# REGULATEUR.net
KiCad netlist of a schematic drawn in Altium Designer
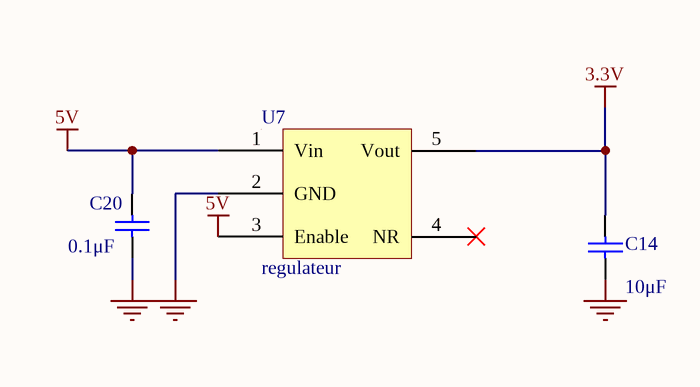
[diagram p0: REGULATEUR.SchDoc]

(export (version "E")
  (design (tool "Eeschema 10.0.6"))
  (components
    (comp (ref "C14")
      (value "10μF")
      (footprint "cond")
      (description "Capacitor")
      (fields (field (name "Comment") "Cap") (field (name "PUBLISHER") "Altium Limited"))
      (libsource (lib "Miscellaneous Devices") (part "Cap"))
    )
    (comp (ref "C20")
      (value "0.1μF")
      (footprint "cond")
      (description "Capacitor")
      (fields (field (name "Comment") "Cap") (field (name "PUBLISHER") "Altium Limited"))
      (libsource (lib "Miscellaneous Devices") (part "Cap"))
    )
    (comp (ref "U7")
      (value "regulateur")
      (footprint "regulateur")
      (libsource (lib "Schlib1") (part "regulateur"))
    )
  )
  (nets
    (net (code "1") (name "3.3V") (class "Default")
      (node (ref "C14") (pin "2") (pinfunction "2_2") (pintype "passive"))
      (node (ref "U7") (pin "5") (pinfunction "Vout_5") (pintype "passive"))
    )
    (net (code "2") (name "5V") (class "Default")
      (node (ref "C20") (pin "2") (pinfunction "2_2") (pintype "passive"))
      (node (ref "U7") (pin "1") (pinfunction "Vin_1") (pintype "power_in"))
      (node (ref "U7") (pin "3") (pinfunction "Enable_3") (pintype "passive"))
    )
    (net (code "3") (name "GND") (class "Default")
      (node (ref "C14") (pin "1") (pinfunction "1_1") (pintype "passive"))
      (node (ref "C20") (pin "1") (pinfunction "1_1") (pintype "passive"))
      (node (ref "U7") (pin "2") (pinfunction "GND_2") (pintype "passive"))
    )
    (net (code "4") (name "unconnected-(U7-NR-Pad4)") (class "Default")
      (node (ref "U7") (pin "4") (pinfunction "NR_4") (pintype "passive+no_connect"))
    )
  )
)
